# SENSE_ADC_-_8CH.net
KiCad netlist of a schematic drawn in Altium Designer
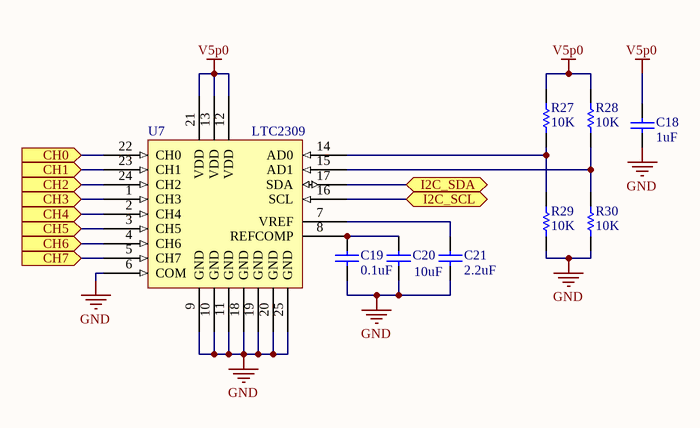
[diagram p0: SENSE ADC - 8CH.SchDoc]

(export (version "E")
  (design (tool "Eeschema 10.0.6"))
  (components
    (comp (ref "C18")
      (value "1uF")
      (footprint "CAPC01005(0402)22_N")
      (fields (field (name "Comment") "CAP, 0402, 1uF"))
      (libsource (lib "Components") (part "CAP, 0402, 1uF"))
    )
    (comp (ref "C19")
      (value "0.1uF")
      (footprint "CAPC01005(0402)22_N")
      (fields (field (name "Comment") "CAP, 0402, 0.1uF"))
      (libsource (lib "Components") (part "CAP, 0402, 0.1uF"))
    )
    (comp (ref "C20")
      (value "10uF")
      (footprint "CAPC0805(2012)130_N")
      (fields (field (name "Comment") "CAP, 0805, 10uF"))
      (libsource (lib "Components") (part "CAP, 0805, 10uF"))
    )
    (comp (ref "C21")
      (value "2.2uF")
      (footprint "CAPC01005(0402)22_N")
      (fields
        (field (name "TOLERANCE") "±20%")
        (field (name "MANUFACTURER") "Taiyo Yuden")
        (field (name "MANUFACTURER PART NUMBER") "EMK105ABJ225MV-F")
      )
      (libsource (lib "Components") (part "CAP, 0402, 2.2uF"))
    )
    (comp (ref "R27")
      (value "10K")
      (footprint "RES, 0603")
      (description "Resistor, 0603, 1/10W, 10K ohm")
      (fields
        (field (name "MANUFACTURER") "Panasonic Electronic Components")
        (field (name "MANUFACTURER PART NUMBER") "ERJ-3EKF1002V")
      )
      (libsource (lib "Resistors0603") (part "RES_0603_10K"))
    )
    (comp (ref "R28")
      (value "10K")
      (footprint "RES, 0603")
      (description "Resistor, 0603, 1/10W, 10K ohm")
      (fields
        (field (name "MANUFACTURER") "Panasonic Electronic Components")
        (field (name "MANUFACTURER PART NUMBER") "ERJ-3EKF1002V")
      )
      (libsource (lib "Resistors0603") (part "RES_0603_10K"))
    )
    (comp (ref "R29")
      (value "10K")
      (footprint "RES, 0603")
      (description "Resistor, 0603, 1/10W, 10K ohm")
      (fields
        (field (name "MANUFACTURER") "Panasonic Electronic Components")
        (field (name "MANUFACTURER PART NUMBER") "ERJ-3EKF1002V")
      )
      (libsource (lib "Resistors0603") (part "RES_0603_10K"))
    )
    (comp (ref "R30")
      (value "10K")
      (footprint "RES, 0603")
      (description "Resistor, 0603, 1/10W, 10K ohm")
      (fields
        (field (name "MANUFACTURER") "Panasonic Electronic Components")
        (field (name "MANUFACTURER PART NUMBER") "ERJ-3EKF1002V")
      )
      (libsource (lib "Resistors0603") (part "RES_0603_10K"))
    )
    (comp (ref "U7")
      (value "LTC2309")
      (footprint "QFN50P400X400X80-24N")
      (description "8-Channel, 12-Bit SAR ADC with I2C Interface")
      (fields
        (field (name "MANUFACTURER") "Linear Technology")
        (field (name "MANUFACTURER PART NUMBER") "LTC2309CUF#PBF")
      )
      (libsource (lib "Components") (part "LTC2309"))
    )
  )
  (nets
    (net (code "1") (name "/CH0") (class "Default")
      (node (ref "U7") (pin "22") (pinfunction "CH0_22") (pintype "input"))
    )
    (net (code "2") (name "/CH1") (class "Default")
      (node (ref "U7") (pin "23") (pinfunction "CH1_23") (pintype "input"))
    )
    (net (code "3") (name "/CH2") (class "Default")
      (node (ref "U7") (pin "24") (pinfunction "CH2_24") (pintype "input"))
    )
    (net (code "4") (name "/CH3") (class "Default")
      (node (ref "U7") (pin "1") (pinfunction "CH3_1") (pintype "input"))
    )
    (net (code "5") (name "/CH4") (class "Default")
      (node (ref "U7") (pin "2") (pinfunction "CH4_2") (pintype "input"))
    )
    (net (code "6") (name "/CH5") (class "Default")
      (node (ref "U7") (pin "3") (pinfunction "CH5_3") (pintype "input"))
    )
    (net (code "7") (name "/CH6") (class "Default")
      (node (ref "U7") (pin "4") (pinfunction "CH6_4") (pintype "input"))
    )
    (net (code "8") (name "/CH7") (class "Default")
      (node (ref "U7") (pin "5") (pinfunction "CH7_5") (pintype "input"))
    )
    (net (code "9") (name "/I2C_SCL") (class "Default")
      (node (ref "U7") (pin "16") (pinfunction "SCL_16") (pintype "input"))
    )
    (net (code "10") (name "/I2C_SDA") (class "Default")
      (node (ref "U7") (pin "17") (pinfunction "SDA_17") (pintype "bidirectional"))
    )
    (net (code "11") (name "GND") (class "Default")
      (node (ref "C18") (pin "1") (pinfunction "1_1") (pintype "passive"))
      (node (ref "C19") (pin "1") (pinfunction "1_1") (pintype "passive"))
      (node (ref "C20") (pin "1") (pinfunction "1_1") (pintype "passive"))
      (node (ref "C21") (pin "1") (pinfunction "1_1") (pintype "passive"))
      (node (ref "R29") (pin "2") (pinfunction "2_2") (pintype "passive"))
      (node (ref "R30") (pin "2") (pinfunction "2_2") (pintype "passive"))
      (node (ref "U7") (pin "10") (pinfunction "GND_10") (pintype "power_in"))
      (node (ref "U7") (pin "11") (pinfunction "GND_11") (pintype "power_in"))
      (node (ref "U7") (pin "18") (pinfunction "GND_18") (pintype "power_in"))
      (node (ref "U7") (pin "19") (pinfunction "GND_19") (pintype "power_in"))
      (node (ref "U7") (pin "20") (pinfunction "GND_20") (pintype "power_in"))
      (node (ref "U7") (pin "25") (pinfunction "GND_25") (pintype "power_in"))
      (node (ref "U7") (pin "6") (pinfunction "COM_6") (pintype "input"))
      (node (ref "U7") (pin "9") (pinfunction "GND_9") (pintype "power_in"))
    )
    (net (code "12") (name "Net-(U7-AD0)") (class "Default")
      (node (ref "R27") (pin "2") (pinfunction "2_2") (pintype "passive"))
      (node (ref "R29") (pin "1") (pinfunction "1_1") (pintype "passive"))
      (node (ref "U7") (pin "14") (pinfunction "AD0_14") (pintype "input"))
    )
    (net (code "13") (name "Net-(U7-AD1)") (class "Default")
      (node (ref "R28") (pin "2") (pinfunction "2_2") (pintype "passive"))
      (node (ref "R30") (pin "1") (pinfunction "1_1") (pintype "passive"))
      (node (ref "U7") (pin "15") (pinfunction "AD1_15") (pintype "input"))
    )
    (net (code "14") (name "Net-(U7-REFCOMP)") (class "Default")
      (node (ref "C19") (pin "2") (pinfunction "2_2") (pintype "passive"))
      (node (ref "C20") (pin "2") (pinfunction "2_2") (pintype "passive"))
      (node (ref "U7") (pin "8") (pinfunction "REFCOMP_8") (pintype "passive"))
    )
    (net (code "15") (name "Net-(U7-VREF)") (class "Default")
      (node (ref "C21") (pin "2") (pinfunction "2_2") (pintype "passive"))
      (node (ref "U7") (pin "7") (pinfunction "VREF_7") (pintype "passive"))
    )
    (net (code "16") (name "V5p0") (class "Default")
      (node (ref "C18") (pin "2") (pinfunction "2_2") (pintype "passive"))
      (node (ref "R27") (pin "1") (pinfunction "1_1") (pintype "passive"))
      (node (ref "R28") (pin "1") (pinfunction "1_1") (pintype "passive"))
      (node (ref "U7") (pin "12") (pinfunction "VDD_12") (pintype "power_in"))
      (node (ref "U7") (pin "13") (pinfunction "VDD_13") (pintype "power_in"))
      (node (ref "U7") (pin "21") (pinfunction "VDD_21") (pintype "power_in"))
    )
  )
)
